# 1_DotexBoard_MCU.net
KiCad netlist of a schematic drawn in Altium Designer
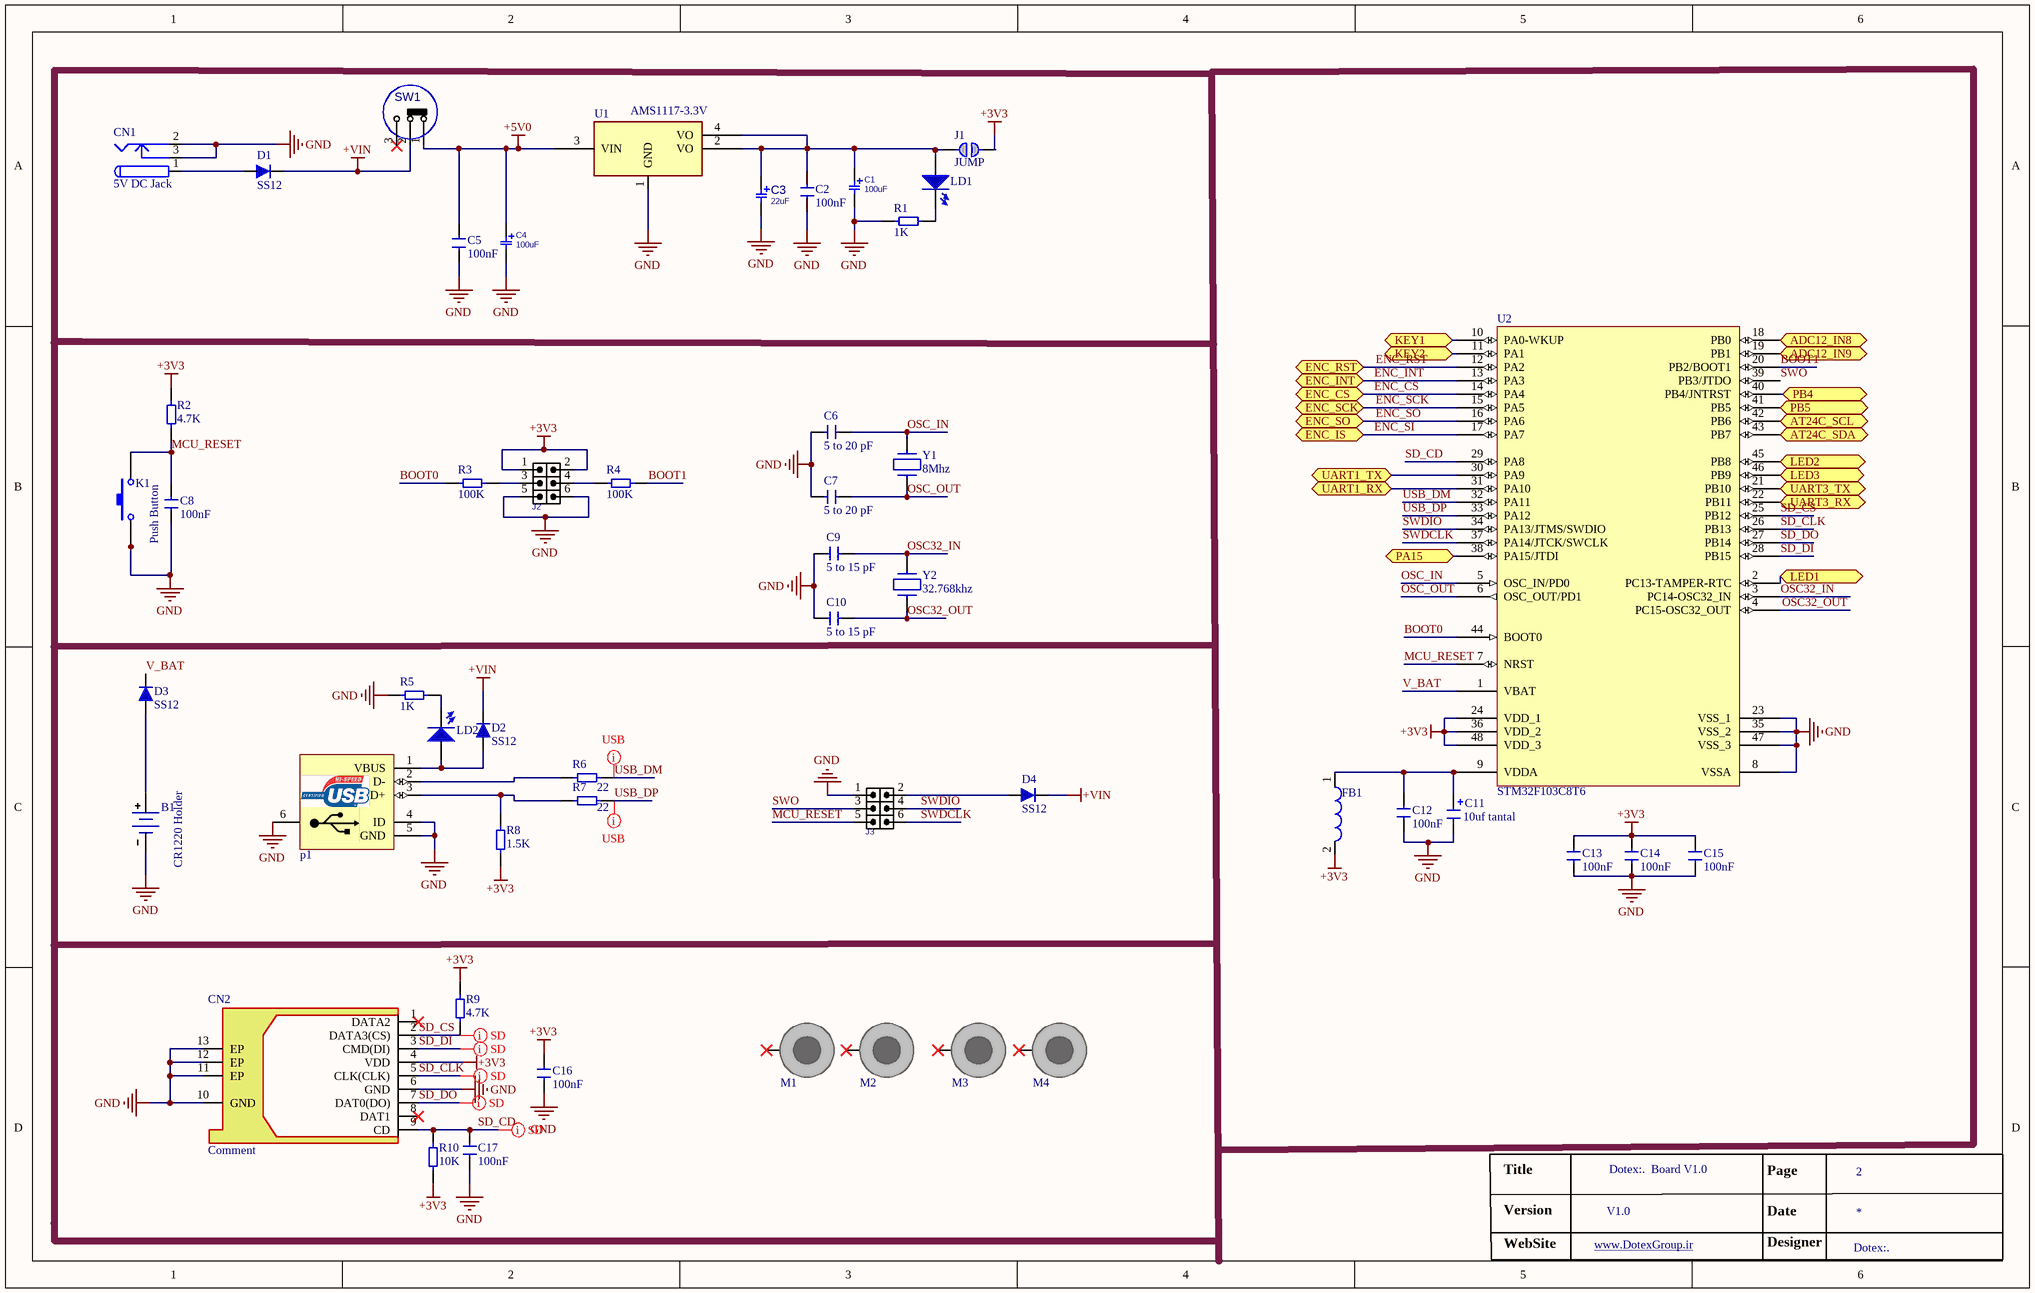
[diagram p0: [1]DotexBoard_MCU.SchDoc]

(export (version "E")
  (design (tool "Eeschema 10.0.6"))
  (components
    (comp (ref "B1")
      (value "CR1220 Holder")
      (footprint "Battery socket SMD")
      (libsource (lib "DotexGroup_LIB") (part "Battry Backup"))
    )
    (comp (ref "C1")
      (value "100uF")
      (footprint "C_EL_6_6")
      (description "CAP, THD, ELEC, 10uF, 25V")
      (fields (field (name "MANF") "MANF") (field (name "MANF_P#") "MANF_PART#"))
      (libsource (lib "DotexGroup_LIB") (part "CAP_THD_EL_10u25V"))
    )
    (comp (ref "C2")
      (value "Comment")
      (footprint "0805 Capacitor")
      (fields (field (name "ALTIUM_UNNAMED_1") "100nF"))
      (libsource (lib "DotexGroup_LIB") (part "Capacitor SMD"))
    )
    (comp (ref "C3")
      (value "22uF")
      (footprint "C_EL_5")
      (description "CAP, SMDD, ELEC, 100uF, 10V")
      (fields (field (name "MANF_P#") "875105242010") (field (name "MANF") "Wurth Electronics"))
      (libsource (lib "DotexGroup_LIB") (part "CAP_SMD_EL_100u10V"))
    )
    (comp (ref "C4")
      (value "100uF")
      (footprint "C_EL_6_6")
      (description "CAP, THD, ELEC, 10uF, 25V")
      (fields (field (name "MANF") "MANF") (field (name "MANF_P#") "MANF_PART#"))
      (libsource (lib "DotexGroup_LIB") (part "CAP_THD_EL_10u25V"))
    )
    (comp (ref "C5")
      (value "Comment")
      (footprint "0805 Capacitor")
      (fields (field (name "ALTIUM_UNNAMED_1") "100nF"))
      (libsource (lib "DotexGroup_LIB") (part "Capacitor SMD"))
    )
    (comp (ref "C6")
      (value "Comment")
      (footprint "0805 Capacitor")
      (fields (field (name "ALTIUM_UNNAMED_1") "5 to 20 pF"))
      (libsource (lib "DotexGroup_LIB") (part "Capacitor SMD"))
    )
    (comp (ref "C7")
      (value "Comment")
      (footprint "0805 Capacitor")
      (fields (field (name "ALTIUM_UNNAMED_1") "5 to 20 pF"))
      (libsource (lib "DotexGroup_LIB") (part "Capacitor SMD"))
    )
    (comp (ref "C8")
      (value "Comment")
      (footprint "0805 Capacitor")
      (fields (field (name "ALTIUM_UNNAMED_1") "100nF"))
      (libsource (lib "DotexGroup_LIB") (part "Capacitor SMD"))
    )
    (comp (ref "C9")
      (value "Comment")
      (footprint "0805 Capacitor")
      (fields (field (name "ALTIUM_UNNAMED_1") "5 to 15 pF"))
      (libsource (lib "DotexGroup_LIB") (part "Capacitor SMD"))
    )
    (comp (ref "C10")
      (value "Comment")
      (footprint "0805 Capacitor")
      (fields (field (name "ALTIUM_UNNAMED_1") "5 to 15 pF"))
      (libsource (lib "DotexGroup_LIB") (part "Capacitor SMD"))
    )
    (comp (ref "C11")
      (value "10uf tantal")
      (footprint "Tantalium Size A")
      (libsource (lib "DotexGroup_LIB") (part "Capacitor Tantalium"))
    )
    (comp (ref "C12")
      (value "Comment")
      (footprint "0805 Capacitor")
      (fields (field (name "ALTIUM_UNNAMED_1") "100nF"))
      (libsource (lib "DotexGroup_LIB") (part "Capacitor SMD"))
    )
    (comp (ref "C13")
      (value "Comment")
      (footprint "0805 Capacitor")
      (fields (field (name "ALTIUM_UNNAMED_1") "100nF"))
      (libsource (lib "DotexGroup_LIB") (part "Capacitor SMD"))
    )
    (comp (ref "C14")
      (value "Comment")
      (footprint "0805 Capacitor")
      (fields (field (name "ALTIUM_UNNAMED_1") "100nF"))
      (libsource (lib "DotexGroup_LIB") (part "Capacitor SMD"))
    )
    (comp (ref "C15")
      (value "Comment")
      (footprint "0805 Capacitor")
      (fields (field (name "ALTIUM_UNNAMED_1") "100nF"))
      (libsource (lib "DotexGroup_LIB") (part "Capacitor SMD"))
    )
    (comp (ref "C16")
      (value "Comment")
      (footprint "0805 Capacitor")
      (fields (field (name "ALTIUM_UNNAMED_1") "100nF"))
      (libsource (lib "DotexGroup_LIB") (part "Capacitor SMD"))
    )
    (comp (ref "C17")
      (value "Comment")
      (footprint "0805 Capacitor")
      (fields (field (name "ALTIUM_UNNAMED_1") "100nF"))
      (libsource (lib "DotexGroup_LIB") (part "Capacitor SMD"))
    )
    (comp (ref "CN1")
      (value "5V DC Jack")
      (footprint "Power Jack")
      (libsource (lib "DotexGroup_LIB") (part "Power Jack"))
    )
    (comp (ref "CN2")
      (value "Comment")
      (footprint "Micro SD Card")
      (libsource (lib "DotexGroup_LIB") (part "Micro SD Card"))
    )
    (comp (ref "D1")
      (value "SS12")
      (footprint "DO-214AC(SMA)")
      (libsource (lib "DotexGroup_LIB") (part "1N4001"))
    )
    (comp (ref "D2")
      (value "SS12")
      (footprint "DO-214AC(SMA)")
      (libsource (lib "DotexGroup_LIB") (part "1N4001"))
    )
    (comp (ref "D3")
      (value "SS12")
      (footprint "DO-214AC(SMA)")
      (libsource (lib "DotexGroup_LIB") (part "1N4001"))
    )
    (comp (ref "D4")
      (value "SS12")
      (footprint "DO-214AC(SMA)")
      (libsource (lib "DotexGroup_LIB") (part "1N4001"))
    )
    (comp (ref "FB1")
      (value "Comment")
      (footprint "0805 Ferrit Bead")
      (libsource (lib "DotexGroup_LIB") (part "Ferrit Bead"))
    )
    (comp (ref "J1")
      (value "JUMP")
      (footprint "0805 Capacitor")
      (libsource (lib "DotexGroup_LIB") (part "jumper SMD"))
    )
    (comp (ref "J2")
      (value "HDRM_2X3")
      (footprint "HDR_M_2X3")
      (description "CONN, HEADER, Male, pitch: 2.54mm, 6POS")
      (fields (field (name "MANF_P#") "MANF_PART#") (field (name "MANF") "MANF"))
      (libsource (lib "DotexGroup_LIB") (part "HDR_M_2X3"))
    )
    (comp (ref "J3")
      (value "HDRM_2X3")
      (footprint "HDR_M_2X3")
      (description "CONN, HEADER, Male, pitch: 2.54mm, 6POS")
      (fields (field (name "MANF_P#") "MANF_PART#") (field (name "MANF") "MANF"))
      (libsource (lib "DotexGroup_LIB") (part "HDR_M_2X3"))
    )
    (comp (ref "K1")
      (value "Push Button")
      (footprint "Push Kay 4 KFC")
      (libsource (lib "DotexGroup_LIB") (part "Push Kay"))
    )
    (comp (ref "LD1")
      (value "LED")
      (footprint "LED_0805 Y")
      (libsource (lib "DotexGroup_LIB") (part "LED SMD"))
    )
    (comp (ref "LD2")
      (value "LED")
      (footprint "LED_0805 Y")
      (libsource (lib "DotexGroup_LIB") (part "LED SMD"))
    )
    (comp (ref "M1")
      (value "Comment")
      (footprint "SCMH_M3")
      (description "SCREW mouting, M1.6, 1.6mm diameter and 3.2mm PanHead")
      (libsource (lib "DotexGroup_LIB") (part "SCMH_M1P6"))
    )
    (comp (ref "M2")
      (value "Comment")
      (footprint "SCMH_M3")
      (description "SCREW mouting, M1.6, 1.6mm diameter and 3.2mm PanHead")
      (libsource (lib "DotexGroup_LIB") (part "SCMH_M1P6"))
    )
    (comp (ref "M3")
      (value "Comment")
      (footprint "SCMH_M3")
      (description "SCREW mouting, M1.6, 1.6mm diameter and 3.2mm PanHead")
      (libsource (lib "DotexGroup_LIB") (part "SCMH_M1P6"))
    )
    (comp (ref "M4")
      (value "Comment")
      (footprint "SCMH_M3")
      (description "SCREW mouting, M1.6, 1.6mm diameter and 3.2mm PanHead")
      (libsource (lib "DotexGroup_LIB") (part "SCMH_M1P6"))
    )
    (comp (ref "p1")
      (value "USB Connector")
      (footprint "USB_AB_BM_SHS")
      (description "USB MICRO-B Type Connector")
      (fields (field (name "DESIGNER") "ABBAS BASEREH") (field (name "PUBLISHER") "ABBAS BASEREH"))
      (libsource (lib "DotexGroup_LIB") (part "USB AB MICRO CONNECTOR"))
    )
    (comp (ref "R1")
      (value "Comment")
      (footprint "0805 Resistor")
      (fields (field (name "ALTIUM_UNNAMED_1") "1K"))
      (libsource (lib "DotexGroup_LIB") (part "Resistor SMD"))
    )
    (comp (ref "R2")
      (value "Comment")
      (footprint "0805 Resistor")
      (fields (field (name "ALTIUM_UNNAMED_1") "4.7K"))
      (libsource (lib "DotexGroup_LIB") (part "Resistor SMD"))
    )
    (comp (ref "R3")
      (value "Comment")
      (footprint "0805 Resistor")
      (fields (field (name "ALTIUM_UNNAMED_1") "100K"))
      (libsource (lib "DotexGroup_LIB") (part "Resistor SMD"))
    )
    (comp (ref "R4")
      (value "Comment")
      (footprint "0805 Resistor")
      (fields (field (name "ALTIUM_UNNAMED_1") "100K"))
      (libsource (lib "DotexGroup_LIB") (part "Resistor SMD"))
    )
    (comp (ref "R5")
      (value "Comment")
      (footprint "0805 Resistor")
      (fields (field (name "ALTIUM_UNNAMED_1") "1K"))
      (libsource (lib "DotexGroup_LIB") (part "Resistor SMD"))
    )
    (comp (ref "R6")
      (value "Comment")
      (footprint "0805 Resistor")
      (fields (field (name "ALTIUM_UNNAMED_1") "22"))
      (libsource (lib "DotexGroup_LIB") (part "Resistor SMD"))
    )
    (comp (ref "R7")
      (value "Comment")
      (footprint "0805 Resistor")
      (fields (field (name "ALTIUM_UNNAMED_1") "22"))
      (libsource (lib "DotexGroup_LIB") (part "Resistor SMD"))
    )
    (comp (ref "R8")
      (value "Comment")
      (footprint "0805 Resistor")
      (fields (field (name "ALTIUM_UNNAMED_1") "1.5K"))
      (libsource (lib "DotexGroup_LIB") (part "Resistor SMD"))
    )
    (comp (ref "R9")
      (value "Comment")
      (footprint "0805 Resistor")
      (fields (field (name "ALTIUM_UNNAMED_1") "4.7K"))
      (libsource (lib "DotexGroup_LIB") (part "Resistor SMD"))
    )
    (comp (ref "R10")
      (value "Comment")
      (footprint "0805 Resistor")
      (fields (field (name "ALTIUM_UNNAMED_1") "10K"))
      (libsource (lib "DotexGroup_LIB") (part "Resistor SMD"))
    )
    (comp (ref "SW1")
      (value "SlideSwitch")
      (footprint "SWSLIDT_SPDT_R_8X4")
      (description "SWITCH, SLIDE, SPDT, 8.6X4.3mm, THD")
      (fields (field (name "MANF") "C&K") (field (name "MANF_PART#") "OS102011MS2QN1"))
      (libsource (lib "DotexGroup_LIB") (part "SWSLIDT_SPDT_S_8X4"))
    )
    (comp (ref "U1")
      (value "AMS1117-3.3V")
      (footprint "SOT223_4")
      (description "REG, Linear, LDO1V, 0.8A, SOT-223")
      (fields
        (field (name "MANF_P#") "LD1117, LM1117, AMS1117, TLV1117, REG1117, NCP1117, LT1117, SPX1117")
        (field (name "MANF") "TI, ON, ST")
      )
      (libsource (lib "DotexGroup_LIB") (part "VREG_1117_SOT223"))
    )
    (comp (ref "U2")
      (value "STM32F103C8T6")
      (footprint "LQFP48_N")
      (description "STM32 ARM-based 32-bit MCU with 64 Kbytes Flash, 48-pin LQFP, Industrial Temperature")
      (fields (field (name "PUBLISHER") "Altium Limited"))
      (libsource (lib "DotexGroup_LIB") (part "STM32F103C8T6"))
    )
    (comp (ref "Y1") (value "8Mhz") (footprint "Xtal 2p") (libsource (lib "DotexGroup_LIB") (part "Xtal")))
    (comp (ref "Y2")
      (value "32.768khz")
      (footprint "Xtal 32.782khz")
      (libsource (lib "DotexGroup_LIB") (part "Xtal"))
    )
  )
  (nets
    (net (code "1") (name "+3V3") (class "Default")
      (node (ref "C13") (pin "2") (pintype "passive"))
      (node (ref "C14") (pin "2") (pintype "passive"))
      (node (ref "C15") (pin "2") (pintype "passive"))
      (node (ref "C16") (pin "2") (pintype "passive"))
      (node (ref "CN2") (pin "4") (pinfunction "VDD_4") (pintype "passive"))
      (node (ref "FB1") (pin "2") (pinfunction "2_2") (pintype "passive"))
      (node (ref "J1") (pin "2") (pintype "passive"))
      (node (ref "J2") (pin "1") (pinfunction "1_1") (pintype "passive"))
      (node (ref "J2") (pin "2") (pinfunction "2_2") (pintype "passive"))
      (node (ref "R10") (pin "2") (pintype "passive"))
      (node (ref "R2") (pin "1") (pintype "passive"))
      (node (ref "R8") (pin "1") (pintype "passive"))
      (node (ref "R9") (pin "1") (pintype "passive"))
      (node (ref "U2") (pin "24") (pinfunction "VDD_1_24") (pintype "power_in"))
      (node (ref "U2") (pin "36") (pinfunction "VDD_2_36") (pintype "power_in"))
      (node (ref "U2") (pin "48") (pinfunction "VDD_3_48") (pintype "power_in"))
    )
    (net (code "2") (name "+5V0") (class "Default")
      (node (ref "C4") (pin "1") (pinfunction "1_1") (pintype "passive"))
      (node (ref "C5") (pin "2") (pintype "passive"))
      (node (ref "SW1") (pin "1") (pinfunction "P1_1") (pintype "passive"))
      (node (ref "U1") (pin "3") (pinfunction "VIN_3") (pintype "passive"))
    )
    (net (code "3") (name "+VIN") (class "Default")
      (node (ref "D1") (pin "2") (pinfunction "K_2") (pintype "passive"))
      (node (ref "D2") (pin "2") (pinfunction "K_2") (pintype "passive"))
      (node (ref "D4") (pin "2") (pinfunction "K_2") (pintype "passive"))
      (node (ref "SW1") (pin "2") (pinfunction "P3_2") (pintype "passive"))
    )
    (net (code "4") (name "/ADC12_IN8") (class "Default")
      (node (ref "U2") (pin "18") (pinfunction "PB0_18") (pintype "bidirectional"))
    )
    (net (code "5") (name "/ADC12_IN9") (class "Default")
      (node (ref "U2") (pin "19") (pinfunction "PB1_19") (pintype "bidirectional"))
    )
    (net (code "6") (name "/AT24C_SCL") (class "Default")
      (node (ref "U2") (pin "42") (pinfunction "PB6_42") (pintype "bidirectional"))
    )
    (net (code "7") (name "/AT24C_SDA") (class "Default")
      (node (ref "U2") (pin "43") (pinfunction "PB7_43") (pintype "bidirectional"))
    )
    (net (code "8") (name "/BOOT0") (class "Default")
      (node (ref "R3") (pin "1") (pintype "passive"))
      (node (ref "U2") (pin "44") (pinfunction "BOOT0_44") (pintype "input"))
    )
    (net (code "9") (name "/BOOT1") (class "Default")
      (node (ref "R4") (pin "2") (pintype "passive"))
      (node (ref "U2") (pin "20") (pinfunction "PB2/BOOT1_20") (pintype "bidirectional"))
    )
    (net (code "10") (name "/ENC_CS") (class "Default")
      (node (ref "U2") (pin "14") (pinfunction "PA4_14") (pintype "bidirectional"))
    )
    (net (code "11") (name "/ENC_INT") (class "Default")
      (node (ref "U2") (pin "13") (pinfunction "PA3_13") (pintype "bidirectional"))
    )
    (net (code "12") (name "/ENC_RST") (class "Default")
      (node (ref "U2") (pin "12") (pinfunction "PA2_12") (pintype "bidirectional"))
    )
    (net (code "13") (name "/ENC_SCK") (class "Default")
      (node (ref "U2") (pin "15") (pinfunction "PA5_15") (pintype "bidirectional"))
    )
    (net (code "14") (name "/ENC_SI") (class "Default")
      (node (ref "U2") (pin "17") (pinfunction "PA7_17") (pintype "bidirectional"))
    )
    (net (code "15") (name "/ENC_SO") (class "Default")
      (node (ref "U2") (pin "16") (pinfunction "PA6_16") (pintype "bidirectional"))
    )
    (net (code "16") (name "/KEY1") (class "Default")
      (node (ref "U2") (pin "10") (pinfunction "PA0-WKUP_10") (pintype "bidirectional"))
    )
    (net (code "17") (name "/KEY2") (class "Default")
      (node (ref "U2") (pin "11") (pinfunction "PA1_11") (pintype "bidirectional"))
    )
    (net (code "18") (name "/LED1") (class "Default")
      (node (ref "U2") (pin "2") (pinfunction "PC13-TAMPER-RTC_2") (pintype "bidirectional"))
    )
    (net (code "19") (name "/LED2") (class "Default")
      (node (ref "U2") (pin "45") (pinfunction "PB8_45") (pintype "bidirectional"))
    )
    (net (code "20") (name "/LED3") (class "Default")
      (node (ref "U2") (pin "46") (pinfunction "PB9_46") (pintype "bidirectional"))
    )
    (net (code "21") (name "/MCU_RESET") (class "Default")
      (node (ref "C8") (pin "1") (pintype "passive"))
      (node (ref "J3") (pin "5") (pinfunction "5_5") (pintype "passive"))
      (node (ref "K1") (pin "2") (pinfunction "2_2") (pintype "passive"))
      (node (ref "R2") (pin "2") (pintype "passive"))
      (node (ref "U2") (pin "7") (pinfunction "NRST_7") (pintype "bidirectional"))
    )
    (net (code "22") (name "/OSC32_IN") (class "Default")
      (node (ref "C9") (pin "2") (pintype "passive"))
      (node (ref "U2") (pin "3") (pinfunction "PC14-OSC32_IN_3") (pintype "bidirectional"))
      (node (ref "Y2") (pin "1") (pintype "passive"))
    )
    (net (code "23") (name "/OSC32_OUT") (class "Default")
      (node (ref "C10") (pin "1") (pintype "passive"))
      (node (ref "U2") (pin "4") (pinfunction "PC15-OSC32_OUT_4") (pintype "bidirectional"))
      (node (ref "Y2") (pin "2") (pintype "passive"))
    )
    (net (code "24") (name "/OSC_IN") (class "Default")
      (node (ref "C6") (pin "2") (pintype "passive"))
      (node (ref "U2") (pin "5") (pinfunction "OSC_IN/PD0_5") (pintype "input"))
      (node (ref "Y1") (pin "2") (pintype "passive"))
    )
    (net (code "25") (name "/OSC_OUT") (class "Default")
      (node (ref "C7") (pin "1") (pintype "passive"))
      (node (ref "U2") (pin "6") (pinfunction "OSC_OUT/PD1_6") (pintype "output"))
      (node (ref "Y1") (pin "1") (pintype "passive"))
    )
    (net (code "26") (name "/PA15") (class "Default")
      (node (ref "U2") (pin "38") (pinfunction "PA15/JTDI_38") (pintype "bidirectional"))
    )
    (net (code "27") (name "/PB4") (class "Default")
      (node (ref "U2") (pin "40") (pinfunction "PB4/JNTRST_40") (pintype "bidirectional"))
    )
    (net (code "28") (name "/PB5") (class "Default")
      (node (ref "U2") (pin "41") (pinfunction "PB5_41") (pintype "bidirectional"))
    )
    (net (code "29") (name "/SD_CD") (class "Default")
      (node (ref "C17") (pin "1") (pintype "passive"))
      (node (ref "CN2") (pin "9") (pinfunction "CD_9") (pintype "passive"))
      (node (ref "R10") (pin "1") (pintype "passive"))
      (node (ref "U2") (pin "29") (pinfunction "PA8_29") (pintype "bidirectional"))
    )
    (net (code "30") (name "/SD_CLK") (class "Default")
      (node (ref "CN2") (pin "5") (pinfunction "CLK(CLK)_5") (pintype "passive"))
      (node (ref "U2") (pin "26") (pinfunction "PB13_26") (pintype "bidirectional"))
    )
    (net (code "31") (name "/SD_CS") (class "Default")
      (node (ref "CN2") (pin "2") (pinfunction "DATA3(CS)_2") (pintype "passive"))
      (node (ref "R9") (pin "2") (pintype "passive"))
      (node (ref "U2") (pin "25") (pinfunction "PB12_25") (pintype "bidirectional"))
    )
    (net (code "32") (name "/SD_DI") (class "Default")
      (node (ref "CN2") (pin "3") (pinfunction "CMD(DI)_3") (pintype "passive"))
      (node (ref "U2") (pin "28") (pinfunction "PB15_28") (pintype "bidirectional"))
    )
    (net (code "33") (name "/SD_DO") (class "Default")
      (node (ref "CN2") (pin "7") (pinfunction "DAT0(DO)_7") (pintype "passive"))
      (node (ref "U2") (pin "27") (pinfunction "PB14_27") (pintype "bidirectional"))
    )
    (net (code "34") (name "/SWDCLK") (class "Default")
      (node (ref "J3") (pin "6") (pinfunction "6_6") (pintype "passive"))
      (node (ref "U2") (pin "37") (pinfunction "PA14/JTCK/SWCLK_37") (pintype "bidirectional"))
    )
    (net (code "35") (name "/SWDIO") (class "Default")
      (node (ref "J3") (pin "4") (pinfunction "4_4") (pintype "passive"))
      (node (ref "U2") (pin "34") (pinfunction "PA13/JTMS/SWDIO_34") (pintype "bidirectional"))
    )
    (net (code "36") (name "/SWO") (class "Default")
      (node (ref "J3") (pin "3") (pinfunction "3_3") (pintype "passive"))
      (node (ref "U2") (pin "39") (pinfunction "PB3/JTDO_39") (pintype "bidirectional"))
    )
    (net (code "37") (name "/UART1_RX") (class "Default")
      (node (ref "U2") (pin "31") (pinfunction "PA10_31") (pintype "bidirectional"))
    )
    (net (code "38") (name "/UART1_TX") (class "Default")
      (node (ref "U2") (pin "30") (pinfunction "PA9_30") (pintype "bidirectional"))
    )
    (net (code "39") (name "/UART3_RX") (class "Default")
      (node (ref "U2") (pin "22") (pinfunction "PB11_22") (pintype "bidirectional"))
    )
    (net (code "40") (name "/UART3_TX") (class "Default")
      (node (ref "U2") (pin "21") (pinfunction "PB10_21") (pintype "bidirectional"))
    )
    (net (code "41") (name "/USB_DM") (class "Default")
      (node (ref "R6") (pin "2") (pintype "passive"))
      (node (ref "U2") (pin "32") (pinfunction "PA11_32") (pintype "bidirectional"))
    )
    (net (code "42") (name "/USB_DP") (class "Default")
      (node (ref "R7") (pin "2") (pintype "passive"))
      (node (ref "U2") (pin "33") (pinfunction "PA12_33") (pintype "bidirectional"))
    )
    (net (code "43") (name "/V_BAT") (class "Default")
      (node (ref "D3") (pin "2") (pinfunction "K_2") (pintype "passive"))
      (node (ref "U2") (pin "1") (pinfunction "VBAT_1") (pintype "power_in"))
    )
    (net (code "44") (name "GND") (class "Default")
      (node (ref "B1") (pin "2") (pinfunction "-_2") (pintype "passive"))
      (node (ref "C1") (pin "2") (pinfunction "2_2") (pintype "passive"))
      (node (ref "C10") (pin "2") (pintype "passive"))
      (node (ref "C11") (pin "2") (pintype "passive"))
      (node (ref "C12") (pin "1") (pintype "passive"))
      (node (ref "C13") (pin "1") (pintype "passive"))
      (node (ref "C14") (pin "1") (pintype "passive"))
      (node (ref "C15") (pin "1") (pintype "passive"))
      (node (ref "C16") (pin "1") (pintype "passive"))
      (node (ref "C17") (pin "2") (pintype "passive"))
      (node (ref "C2") (pin "1") (pintype "passive"))
      (node (ref "C3") (pin "2") (pinfunction "2_2") (pintype "passive"))
      (node (ref "C4") (pin "2") (pinfunction "2_2") (pintype "passive"))
      (node (ref "C5") (pin "1") (pintype "passive"))
      (node (ref "C6") (pin "1") (pintype "passive"))
      (node (ref "C7") (pin "2") (pintype "passive"))
      (node (ref "C8") (pin "2") (pintype "passive"))
      (node (ref "C9") (pin "1") (pintype "passive"))
      (node (ref "CN1") (pin "2") (pinfunction "2_2") (pintype "power_in"))
      (node (ref "CN1") (pin "3") (pinfunction "3_3") (pintype "power_in"))
      (node (ref "CN2") (pin "10") (pinfunction "GND_10") (pintype "passive"))
      (node (ref "CN2") (pin "11") (pinfunction "EP_11") (pintype "passive"))
      (node (ref "CN2") (pin "12") (pinfunction "EP_12") (pintype "passive"))
      (node (ref "CN2") (pin "13") (pinfunction "EP_13") (pintype "passive"))
      (node (ref "CN2") (pin "6") (pinfunction "GND_6") (pintype "passive"))
      (node (ref "J2") (pin "5") (pinfunction "5_5") (pintype "passive"))
      (node (ref "J2") (pin "6") (pinfunction "6_6") (pintype "passive"))
      (node (ref "J3") (pin "1") (pinfunction "1_1") (pintype "passive"))
      (node (ref "K1") (pin "1") (pinfunction "1_1") (pintype "passive"))
      (node (ref "R1") (pin "2") (pintype "passive"))
      (node (ref "R5") (pin "2") (pintype "passive"))
      (node (ref "U1") (pin "1") (pinfunction "GND_1") (pintype "passive"))
      (node (ref "U2") (pin "23") (pinfunction "VSS_1_23") (pintype "power_in"))
      (node (ref "U2") (pin "35") (pinfunction "VSS_2_35") (pintype "power_in"))
      (node (ref "U2") (pin "47") (pinfunction "VSS_3_47") (pintype "power_in"))
      (node (ref "U2") (pin "8") (pinfunction "VSSA_8") (pintype "power_in"))
      (node (ref "p1") (pin "4") (pinfunction "ID_4") (pintype "power_in"))
      (node (ref "p1") (pin "5") (pinfunction "GND_5") (pintype "power_in"))
      (node (ref "p1") (pin "6") (pinfunction "MH_6") (pintype "power_in"))
    )
    (net (code "45") (name "Net-(B1-+)") (class "Default")
      (node (ref "B1") (pin "1") (pinfunction "+_1") (pintype "passive"))
      (node (ref "D3") (pin "1") (pinfunction "A_1") (pintype "passive"))
    )
    (net (code "46") (name "Net-(D1-A)") (class "Default")
      (node (ref "CN1") (pin "1") (pinfunction "1_1") (pintype "power_in"))
      (node (ref "D1") (pin "1") (pinfunction "A_1") (pintype "passive"))
    )
    (net (code "47") (name "Net-(D2-A)") (class "Default")
      (node (ref "D2") (pin "1") (pinfunction "A_1") (pintype "passive"))
      (node (ref "LD2") (pin "1") (pinfunction "A_1") (pintype "passive"))
      (node (ref "p1") (pin "1") (pinfunction "VBUS_1") (pintype "power_in"))
    )
    (net (code "48") (name "Net-(D4-A)") (class "Default")
      (node (ref "D4") (pin "1") (pinfunction "A_1") (pintype "passive"))
      (node (ref "J3") (pin "2") (pinfunction "2_2") (pintype "passive"))
    )
    (net (code "49") (name "Net-(J2-Pad3)") (class "Default")
      (node (ref "J2") (pin "3") (pinfunction "3_3") (pintype "passive"))
      (node (ref "R3") (pin "2") (pintype "passive"))
    )
    (net (code "50") (name "Net-(J2-Pad4)") (class "Default")
      (node (ref "J2") (pin "4") (pinfunction "4_4") (pintype "passive"))
      (node (ref "R4") (pin "1") (pintype "passive"))
    )
    (net (code "51") (name "Net-(LD1-A)") (class "Default")
      (node (ref "C1") (pin "1") (pinfunction "1_1") (pintype "passive"))
      (node (ref "C2") (pin "2") (pintype "passive"))
      (node (ref "C3") (pin "1") (pinfunction "1_1") (pintype "passive"))
      (node (ref "J1") (pin "1") (pintype "passive"))
      (node (ref "LD1") (pin "1") (pinfunction "A_1") (pintype "passive"))
      (node (ref "U1") (pin "2") (pinfunction "VO_2") (pintype "passive"))
      (node (ref "U1") (pin "4") (pinfunction "VO_4") (pintype "passive"))
    )
    (net (code "52") (name "Net-(LD1-K)") (class "Default")
      (node (ref "LD1") (pin "2") (pinfunction "K_2") (pintype "passive"))
      (node (ref "R1") (pin "1") (pintype "passive"))
    )
    (net (code "53") (name "Net-(LD2-K)") (class "Default")
      (node (ref "LD2") (pin "2") (pinfunction "K_2") (pintype "passive"))
      (node (ref "R5") (pin "1") (pintype "passive"))
    )
    (net (code "54") (name "Net-(U2-VDDA)") (class "Default")
      (node (ref "C11") (pin "1") (pintype "passive"))
      (node (ref "C12") (pin "2") (pintype "passive"))
      (node (ref "FB1") (pin "1") (pinfunction "1_1") (pintype "passive"))
      (node (ref "U2") (pin "9") (pinfunction "VDDA_9") (pintype "power_in"))
    )
    (net (code "55") (name "Net-(p1-D+)") (class "Default")
      (node (ref "R7") (pin "1") (pintype "passive"))
      (node (ref "R8") (pin "2") (pintype "passive"))
      (node (ref "p1") (pin "3") (pinfunction "D+_3") (pintype "bidirectional"))
    )
    (net (code "56") (name "Net-(p1-D-)") (class "Default")
      (node (ref "R6") (pin "1") (pintype "passive"))
      (node (ref "p1") (pin "2") (pinfunction "D-_2") (pintype "bidirectional"))
    )
    (net (code "57") (name "unconnected-(CN2-DAT1-Pad8)") (class "Default")
      (node (ref "CN2") (pin "8") (pinfunction "DAT1_8") (pintype "passive+no_connect"))
    )
    (net (code "58") (name "unconnected-(CN2-DATA2-Pad1)") (class "Default")
      (node (ref "CN2") (pin "1") (pinfunction "DATA2_1") (pintype "passive+no_connect"))
    )
    (net (code "59") (name "unconnected-(M1-Pad1)") (class "Default")
      (node (ref "M1") (pin "1") (pinfunction "1_1") (pintype "passive+no_connect"))
    )
    (net (code "60") (name "unconnected-(M2-Pad1)") (class "Default")
      (node (ref "M2") (pin "1") (pinfunction "1_1") (pintype "passive+no_connect"))
    )
    (net (code "61") (name "unconnected-(M3-Pad1)") (class "Default")
      (node (ref "M3") (pin "1") (pinfunction "1_1") (pintype "passive+no_connect"))
    )
    (net (code "62") (name "unconnected-(M4-Pad1)") (class "Default")
      (node (ref "M4") (pin "1") (pinfunction "1_1") (pintype "passive+no_connect"))
    )
    (net (code "63") (name "unconnected-(SW1-P4-Pad3)") (class "Default")
      (node (ref "SW1") (pin "3") (pinfunction "P4_3") (pintype "passive+no_connect"))
    )
  )
)
